# 19_PCIE.net
KiCad netlist of a schematic drawn in Altium Designer
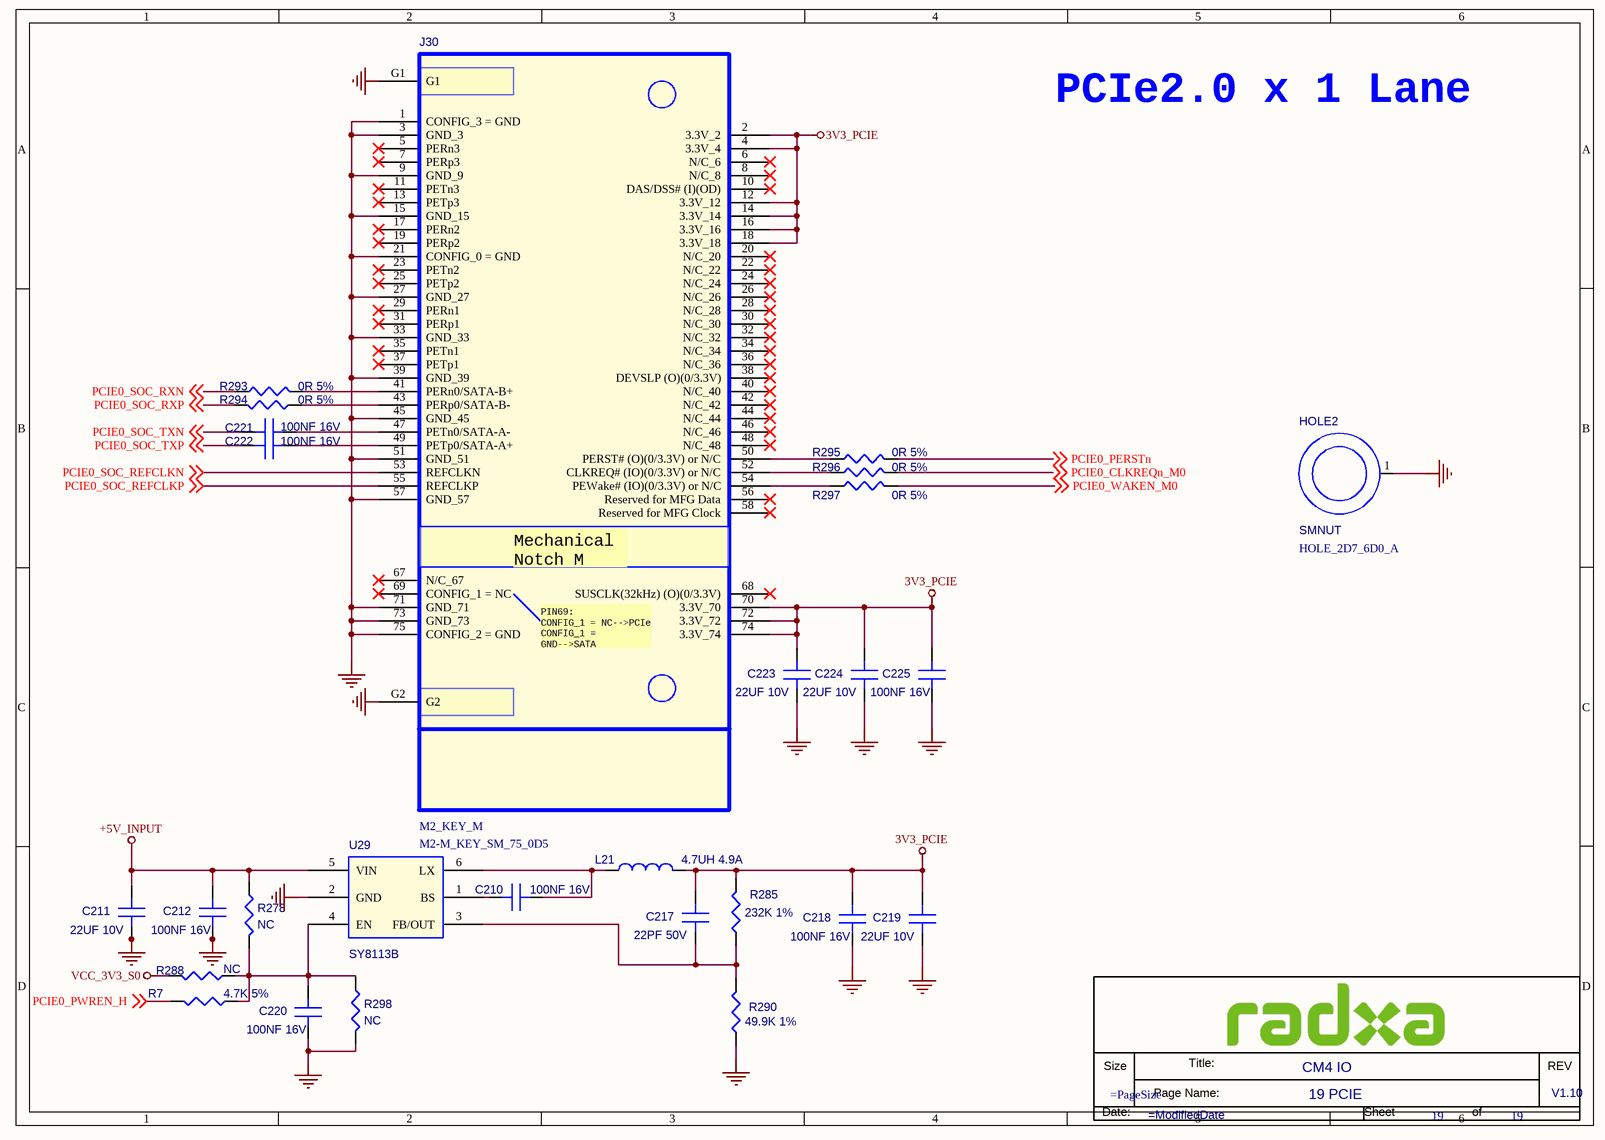
[diagram p0: 19 PCIE.SchDoc]

(export (version "E")
  (design (tool "Eeschema 10.0.6"))
  (components
    (comp (ref "C210")
      (value "100NF 16V")
      (footprint "C0201")
      (description "SMD  0201  100NF  16V  X5R  ±20%  ROHS")
      (fields (field (name "PART NUMBER") "A1C01.00099"))
      (libsource (lib "*") (part "C"))
    )
    (comp (ref "C211")
      (value "22UF 10V")
      (footprint "C0603")
      (description "SMD  0603  22UF  10V  X5R  ±10%  ROHS")
      (fields (field (name "PART NUMBER") "A1C01.00296"))
      (libsource (lib "*") (part "C"))
    )
    (comp (ref "C212")
      (value "100NF 16V")
      (footprint "C0201")
      (description "SMD  0201  100NF  16V  X5R  ±20%  ROHS")
      (fields (field (name "PART NUMBER") "A1C01.00099"))
      (libsource (lib "*") (part "C"))
    )
    (comp (ref "C217")
      (value "22PF 50V")
      (footprint "C0201")
      (description "SMD  0201  22PF  50V  NPO  ±5%  ROHS")
      (fields (field (name "PART NUMBER") "A1C01.00021"))
      (libsource (lib "*") (part "C"))
    )
    (comp (ref "C218")
      (value "100NF 16V")
      (footprint "C0201")
      (description "SMD  0201  100NF  16V  X5R  ±20%  ROHS")
      (fields (field (name "PART NUMBER") "A1C01.00099"))
      (libsource (lib "*") (part "C"))
    )
    (comp (ref "C219")
      (value "22UF 10V")
      (footprint "C0603")
      (description "SMD  0603  22UF  10V  X5R  ±10%  ROHS")
      (fields (field (name "PART NUMBER") "A1C01.00296"))
      (libsource (lib "*") (part "C"))
    )
    (comp (ref "C220")
      (value "100NF 16V")
      (footprint "C0201")
      (description "SMD  0201  100NF  16V  X5R  ±20%  ROHS")
      (fields (field (name "PART NUMBER") "A1C01.00099"))
      (libsource (lib "*") (part "C"))
    )
    (comp (ref "C221")
      (value "100NF 16V")
      (footprint "C0201")
      (description "SMD  0201  100NF  16V  X5R  ±20%  ROHS")
      (fields (field (name "PART NUMBER") "A1C01.00099"))
      (libsource (lib "*") (part "C"))
    )
    (comp (ref "C222")
      (value "100NF 16V")
      (footprint "C0201")
      (description "SMD  0201  100NF  16V  X5R  ±20%  ROHS")
      (fields (field (name "PART NUMBER") "A1C01.00099"))
      (libsource (lib "*") (part "C"))
    )
    (comp (ref "C223")
      (value "22UF 10V")
      (footprint "C0603")
      (description "SMD  0603  22UF  10V  X5R  ±10%  ROHS")
      (fields (field (name "PART NUMBER") "A1C01.00296"))
      (libsource (lib "*") (part "C"))
    )
    (comp (ref "C224")
      (value "22UF 10V")
      (footprint "C0603")
      (description "SMD  0603  22UF  10V  X5R  ±10%  ROHS")
      (fields (field (name "PART NUMBER") "A1C01.00296"))
      (libsource (lib "*") (part "C"))
    )
    (comp (ref "C225")
      (value "100NF 16V")
      (footprint "C0201")
      (description "SMD  0201  100NF  16V  X5R  ±20%  ROHS")
      (fields (field (name "PART NUMBER") "A1C01.00099"))
      (libsource (lib "*") (part "C"))
    )
    (comp (ref "HOLE2")
      (value "SMNUT")
      (footprint "HOLE_2D7_6D0_A")
      (fields (field (name "PART NUMBER") "A1S01.00008") (field (name "PCB FOOTPRINT") "HOLE_2D7_6D0_A"))
      (libsource (lib "*") (part "SMNUT"))
    )
    (comp (ref "J30")
      (value "M2_KEY_M")
      (footprint "M2-M_KEY_SM_75_0D5")
      (description "SMD  母座  75PIN  180度  0.5mm脚距  M.2  M KEY  H8.5  黑色  ROHS")
      (fields (field (name "PART NUMBER") "A1J01.00045") (field (name "PCB FOOTPRINT") "M2-M_KEY_SM_75_0D5"))
      (libsource (lib "*") (part "M2_KEY_M"))
    )
    (comp (ref "L21")
      (value "4.7UH 4.9A")
      (footprint "L_4020")
      (description "SMD  带屏蔽  4*4*2mm  4.7UH  4.9A  ±20%  RXWHJ4020-4R7MT  ROHS")
      (fields (field (name "PART NUMBER") "A1L01.00026"))
      (libsource (lib "*") (part "L"))
    )
    (comp (ref "R7")
      (value "4.7K 5%")
      (footprint "R0402")
      (description "SMD  0201  4.7K  1/20W  ±5%  ROHS")
      (fields (field (name "PART NUMBER") "A1R01.00014"))
      (libsource (lib "*") (part "R"))
    )
    (comp (ref "R278")
      (value "NC")
      (footprint "R0402")
      (description "SMD  0201  10K  1/20W  ±5%  ROHS")
      (fields (field (name "PART NUMBER") "A1R01.00012"))
      (libsource (lib "*") (part "R"))
    )
    (comp (ref "R285")
      (value "232K 1%")
      (footprint "R0402")
      (description "SMD  0201  232K  1/20W  ±1%  ROHS")
      (fields (field (name "PART NUMBER") "A1R01.00189"))
      (libsource (lib "*") (part "R"))
    )
    (comp (ref "R288")
      (value "NC")
      (footprint "R0402")
      (description "SMD  0201  10K  1/20W  ±5%  ROHS")
      (fields (field (name "PART NUMBER") "A1R01.00012"))
      (libsource (lib "*") (part "R"))
    )
    (comp (ref "R290")
      (value "49.9K 1%")
      (footprint "R0402")
      (description "SMD  0201  49.9K  1/20W  ±1%  ROHS")
      (fields (field (name "PART NUMBER") "A1R01.00207"))
      (libsource (lib "*") (part "R"))
    )
    (comp (ref "R293")
      (value "0R 5%")
      (footprint "R0402")
      (description "SMD  0201  0R  1/20W  ±5%  ROHS")
      (fields (field (name "PART NUMBER") "A1R01.00027"))
      (libsource (lib "*") (part "R"))
    )
    (comp (ref "R294")
      (value "0R 5%")
      (footprint "R0402")
      (description "SMD  0201  0R  1/20W  ±5%  ROHS")
      (fields (field (name "PART NUMBER") "A1R01.00027"))
      (libsource (lib "*") (part "R"))
    )
    (comp (ref "R295")
      (value "0R 5%")
      (footprint "R0402")
      (description "SMD  0201  0R  1/20W  ±5%  ROHS")
      (fields (field (name "PART NUMBER") "A1R01.00027"))
      (libsource (lib "*") (part "R"))
    )
    (comp (ref "R296")
      (value "0R 5%")
      (footprint "R0402")
      (description "SMD  0201  0R  1/20W  ±5%  ROHS")
      (fields (field (name "PART NUMBER") "A1R01.00027"))
      (libsource (lib "*") (part "R"))
    )
    (comp (ref "R297")
      (value "0R 5%")
      (footprint "R0402")
      (description "SMD  0201  0R  1/20W  ±5%  ROHS")
      (fields (field (name "PART NUMBER") "A1R01.00027"))
      (libsource (lib "*") (part "R"))
    )
    (comp (ref "R298")
      (value "NC")
      (footprint "R0402")
      (description "SMD  0201  10K  1/20W  ±5%  ROHS")
      (fields (field (name "PART NUMBER") "A1R01.00012"))
      (libsource (lib "*") (part "R"))
    )
    (comp (ref "U29")
      (value "SY8113B")
      (footprint "SOT23_6")
      (description "SMD  DCDC  SY8113BADC  SOT23-6  silergy(矽力杰)  ROHS")
      (fields (field (name "PART NUMBER") "A1I01.00093"))
      (libsource (lib "*") (part "SY8113B"))
    )
  )
  (nets
    (net (code "1") (name "+5V_INPUT") (class "Default")
      (node (ref "C211") (pin "1") (pinfunction "A_1") (pintype "passive"))
      (node (ref "C212") (pin "1") (pinfunction "A_1") (pintype "passive"))
      (node (ref "R278") (pin "2") (pinfunction "2_2") (pintype "passive"))
      (node (ref "U29") (pin "5") (pinfunction "VIN_5") (pintype "passive"))
    )
    (net (code "2") (name "3V3_PCIE") (class "Default")
      (node (ref "C217") (pin "1") (pinfunction "A_1") (pintype "passive"))
      (node (ref "C218") (pin "1") (pinfunction "A_1") (pintype "passive"))
      (node (ref "C219") (pin "1") (pinfunction "A_1") (pintype "passive"))
      (node (ref "C223") (pin "1") (pinfunction "A_1") (pintype "passive"))
      (node (ref "C224") (pin "1") (pinfunction "A_1") (pintype "passive"))
      (node (ref "C225") (pin "1") (pinfunction "A_1") (pintype "passive"))
      (node (ref "J30") (pin "12") (pinfunction "3.3V_12_12") (pintype "passive"))
      (node (ref "J30") (pin "14") (pinfunction "3.3V_14_14") (pintype "passive"))
      (node (ref "J30") (pin "16") (pinfunction "3.3V_16_16") (pintype "passive"))
      (node (ref "J30") (pin "18") (pinfunction "3.3V_18_18") (pintype "passive"))
      (node (ref "J30") (pin "2") (pinfunction "3.3V_2_2") (pintype "passive"))
      (node (ref "J30") (pin "4") (pinfunction "3.3V_4_4") (pintype "passive"))
      (node (ref "J30") (pin "70") (pinfunction "3.3V_70_70") (pintype "passive"))
      (node (ref "J30") (pin "72") (pinfunction "3.3V_72_72") (pintype "passive"))
      (node (ref "J30") (pin "74") (pinfunction "3.3V_74_74") (pintype "passive"))
      (node (ref "L21") (pin "2") (pinfunction "2_2") (pintype "passive"))
      (node (ref "R285") (pin "1") (pinfunction "1_1") (pintype "passive"))
    )
    (net (code "3") (name "GND") (class "Default")
      (node (ref "C211") (pin "2") (pinfunction "B_2") (pintype "passive"))
      (node (ref "C212") (pin "2") (pinfunction "B_2") (pintype "passive"))
      (node (ref "C218") (pin "2") (pinfunction "B_2") (pintype "passive"))
      (node (ref "C219") (pin "2") (pinfunction "B_2") (pintype "passive"))
      (node (ref "C220") (pin "2") (pinfunction "B_2") (pintype "passive"))
      (node (ref "C223") (pin "2") (pinfunction "B_2") (pintype "passive"))
      (node (ref "C224") (pin "2") (pinfunction "B_2") (pintype "passive"))
      (node (ref "C225") (pin "2") (pinfunction "B_2") (pintype "passive"))
      (node (ref "HOLE2") (pin "1") (pinfunction "1_1") (pintype "passive"))
      (node (ref "J30") (pin "1") (pinfunction "CONFIG_3_=_GND_1") (pintype "passive"))
      (node (ref "J30") (pin "15") (pinfunction "GND_15_15") (pintype "passive"))
      (node (ref "J30") (pin "21") (pinfunction "CONFIG_0_=_GND_21") (pintype "passive"))
      (node (ref "J30") (pin "27") (pinfunction "GND_27_27") (pintype "passive"))
      (node (ref "J30") (pin "3") (pinfunction "GND_3_3") (pintype "passive"))
      (node (ref "J30") (pin "33") (pinfunction "GND_33_33") (pintype "passive"))
      (node (ref "J30") (pin "39") (pinfunction "GND_39_39") (pintype "passive"))
      (node (ref "J30") (pin "45") (pinfunction "GND_45_45") (pintype "passive"))
      (node (ref "J30") (pin "51") (pinfunction "GND_51_51") (pintype "passive"))
      (node (ref "J30") (pin "57") (pinfunction "GND_57_57") (pintype "passive"))
      (node (ref "J30") (pin "71") (pinfunction "GND_71_71") (pintype "passive"))
      (node (ref "J30") (pin "73") (pinfunction "GND_73_73") (pintype "passive"))
      (node (ref "J30") (pin "75") (pinfunction "CONFIG_2_=_GND_75") (pintype "passive"))
      (node (ref "J30") (pin "9") (pinfunction "GND_9_9") (pintype "passive"))
      (node (ref "J30") (pin "G1") (pinfunction "G1_G1") (pintype "passive"))
      (node (ref "J30") (pin "G2") (pinfunction "G2_G2") (pintype "passive"))
      (node (ref "R290") (pin "2") (pinfunction "2_2") (pintype "passive"))
      (node (ref "R298") (pin "1") (pinfunction "1_1") (pintype "passive"))
      (node (ref "U29") (pin "2") (pinfunction "GND_2") (pintype "passive"))
    )
    (net (code "4") (name "Net-(C210-A)") (class "Default")
      (node (ref "C210") (pin "1") (pinfunction "A_1") (pintype "passive"))
      (node (ref "U29") (pin "1") (pinfunction "BS_1") (pintype "passive"))
    )
    (net (code "5") (name "Net-(C210-B)") (class "Default")
      (node (ref "C210") (pin "2") (pinfunction "B_2") (pintype "passive"))
      (node (ref "L21") (pin "1") (pinfunction "1_1") (pintype "passive"))
      (node (ref "U29") (pin "6") (pinfunction "LX_6") (pintype "passive"))
    )
    (net (code "6") (name "Net-(C217-B)") (class "Default")
      (node (ref "C217") (pin "2") (pinfunction "B_2") (pintype "passive"))
      (node (ref "R285") (pin "2") (pinfunction "2_2") (pintype "passive"))
      (node (ref "R290") (pin "1") (pinfunction "1_1") (pintype "passive"))
      (node (ref "U29") (pin "3") (pinfunction "FB/OUT_3") (pintype "passive"))
    )
    (net (code "7") (name "Net-(C220-A)") (class "Default")
      (node (ref "C220") (pin "1") (pinfunction "A_1") (pintype "passive"))
      (node (ref "R278") (pin "1") (pinfunction "1_1") (pintype "passive"))
      (node (ref "R288") (pin "2") (pinfunction "2_2") (pintype "passive"))
      (node (ref "R298") (pin "2") (pinfunction "2_2") (pintype "passive"))
      (node (ref "R7") (pin "2") (pinfunction "2_2") (pintype "passive"))
      (node (ref "U29") (pin "4") (pinfunction "EN_4") (pintype "passive"))
    )
    (net (code "8") (name "Net-(C221-B)") (class "Default")
      (node (ref "C221") (pin "2") (pinfunction "B_2") (pintype "passive"))
      (node (ref "J30") (pin "47") (pinfunction "PETn0/SATA-A-_47") (pintype "passive"))
    )
    (net (code "9") (name "Net-(C222-B)") (class "Default")
      (node (ref "C222") (pin "2") (pinfunction "B_2") (pintype "passive"))
      (node (ref "J30") (pin "49") (pinfunction "PETp0/SATA-A+_49") (pintype "passive"))
    )
    (net (code "10") (name "Net-(J30-CLKREQ#_(IO)(0{slash}3.3V)_or_N{slash}C)") (class "Default")
      (node (ref "J30") (pin "52") (pinfunction "CLKREQ#_(IO)(0/3.3V)_or_N/C_52") (pintype "passive"))
      (node (ref "R296") (pin "1") (pinfunction "1_1") (pintype "passive"))
    )
    (net (code "11") (name "Net-(J30-PERST#_(O)(0{slash}3.3V)_or_N{slash}C)") (class "Default")
      (node (ref "J30") (pin "50") (pinfunction "PERST#_(O)(0/3.3V)_or_N/C_50") (pintype "passive"))
      (node (ref "R295") (pin "1") (pinfunction "1_1") (pintype "passive"))
    )
    (net (code "12") (name "Net-(J30-PERn0{slash}SATA-B+)") (class "Default")
      (node (ref "J30") (pin "41") (pinfunction "PERn0/SATA-B+_41") (pintype "passive"))
      (node (ref "R293") (pin "2") (pinfunction "2_2") (pintype "passive"))
    )
    (net (code "13") (name "Net-(J30-PERp0{slash}SATA-B-)") (class "Default")
      (node (ref "J30") (pin "43") (pinfunction "PERp0/SATA-B-_43") (pintype "passive"))
      (node (ref "R294") (pin "2") (pinfunction "2_2") (pintype "passive"))
    )
    (net (code "14") (name "Net-(J30-PEWake#_(IO)(0{slash}3.3V)_or_N{slash}C)") (class "Default")
      (node (ref "J30") (pin "54") (pinfunction "PEWake#_(IO)(0/3.3V)_or_N/C_54") (pintype "passive"))
      (node (ref "R297") (pin "1") (pinfunction "1_1") (pintype "passive"))
    )
    (net (code "15") (name "PCIE0_CLKREQn_M0") (class "Default")
      (node (ref "R296") (pin "2") (pinfunction "2_2") (pintype "passive"))
    )
    (net (code "16") (name "PCIE0_PERSTn") (class "Default")
      (node (ref "R295") (pin "2") (pinfunction "2_2") (pintype "passive"))
    )
    (net (code "17") (name "PCIE0_PWREN_H") (class "Default")
      (node (ref "R7") (pin "1") (pinfunction "1_1") (pintype "passive"))
    )
    (net (code "18") (name "PCIE0_SOC_REFCLKN") (class "Default")
      (node (ref "J30") (pin "53") (pinfunction "REFCLKN_53") (pintype "passive"))
    )
    (net (code "19") (name "PCIE0_SOC_REFCLKP") (class "Default")
      (node (ref "J30") (pin "55") (pinfunction "REFCLKP_55") (pintype "passive"))
    )
    (net (code "20") (name "PCIE0_SOC_RXN") (class "Default")
      (node (ref "R293") (pin "1") (pinfunction "1_1") (pintype "passive"))
    )
    (net (code "21") (name "PCIE0_SOC_RXP") (class "Default")
      (node (ref "R294") (pin "1") (pinfunction "1_1") (pintype "passive"))
    )
    (net (code "22") (name "PCIE0_SOC_TXN") (class "Default")
      (node (ref "C221") (pin "1") (pinfunction "A_1") (pintype "passive"))
    )
    (net (code "23") (name "PCIE0_SOC_TXP") (class "Default")
      (node (ref "C222") (pin "1") (pinfunction "A_1") (pintype "passive"))
    )
    (net (code "24") (name "PCIE0_WAKEN_M0") (class "Default")
      (node (ref "R297") (pin "2") (pinfunction "2_2") (pintype "passive"))
    )
    (net (code "25") (name "VCC_3V3_S0") (class "Default")
      (node (ref "R288") (pin "1") (pinfunction "1_1") (pintype "passive"))
    )
    (net (code "26") (name "unconnected-(J30-CONFIG_1_=_NC-Pad69)") (class "Default")
      (node (ref "J30") (pin "69") (pinfunction "CONFIG_1_=_NC_69") (pintype "passive+no_connect"))
    )
    (net (code "27") (name "unconnected-(J30-DAS{slash}DSS#_(I)(OD)-Pad10)") (class "Default")
      (node (ref "J30") (pin "10") (pinfunction "DAS/DSS#_(I)(OD)_10") (pintype "passive+no_connect"))
    )
    (net (code "28") (name "unconnected-(J30-DEVSLP_(O)(0{slash}3.3V)-Pad38)") (class "Default")
      (node (ref "J30") (pin "38") (pinfunction "DEVSLP_(O)(0/3.3V)_38") (pintype "passive+no_connect"))
    )
    (net (code "29") (name "unconnected-(J30-N{slash}C_6-Pad6)") (class "Default")
      (node (ref "J30") (pin "6") (pinfunction "N/C_6_6") (pintype "passive+no_connect"))
    )
    (net (code "30") (name "unconnected-(J30-N{slash}C_8-Pad8)") (class "Default")
      (node (ref "J30") (pin "8") (pinfunction "N/C_8_8") (pintype "passive+no_connect"))
    )
    (net (code "31") (name "unconnected-(J30-N{slash}C_20-Pad20)") (class "Default")
      (node (ref "J30") (pin "20") (pinfunction "N/C_20_20") (pintype "passive+no_connect"))
    )
    (net (code "32") (name "unconnected-(J30-N{slash}C_22-Pad22)") (class "Default")
      (node (ref "J30") (pin "22") (pinfunction "N/C_22_22") (pintype "passive+no_connect"))
    )
    (net (code "33") (name "unconnected-(J30-N{slash}C_24-Pad24)") (class "Default")
      (node (ref "J30") (pin "24") (pinfunction "N/C_24_24") (pintype "passive+no_connect"))
    )
    (net (code "34") (name "unconnected-(J30-N{slash}C_26-Pad26)") (class "Default")
      (node (ref "J30") (pin "26") (pinfunction "N/C_26_26") (pintype "passive+no_connect"))
    )
    (net (code "35") (name "unconnected-(J30-N{slash}C_28-Pad28)") (class "Default")
      (node (ref "J30") (pin "28") (pinfunction "N/C_28_28") (pintype "passive+no_connect"))
    )
    (net (code "36") (name "unconnected-(J30-N{slash}C_30-Pad30)") (class "Default")
      (node (ref "J30") (pin "30") (pinfunction "N/C_30_30") (pintype "passive+no_connect"))
    )
    (net (code "37") (name "unconnected-(J30-N{slash}C_32-Pad32)") (class "Default")
      (node (ref "J30") (pin "32") (pinfunction "N/C_32_32") (pintype "passive+no_connect"))
    )
    (net (code "38") (name "unconnected-(J30-N{slash}C_34-Pad34)") (class "Default")
      (node (ref "J30") (pin "34") (pinfunction "N/C_34_34") (pintype "passive+no_connect"))
    )
    (net (code "39") (name "unconnected-(J30-N{slash}C_36-Pad36)") (class "Default")
      (node (ref "J30") (pin "36") (pinfunction "N/C_36_36") (pintype "passive+no_connect"))
    )
    (net (code "40") (name "unconnected-(J30-N{slash}C_40-Pad40)") (class "Default")
      (node (ref "J30") (pin "40") (pinfunction "N/C_40_40") (pintype "passive+no_connect"))
    )
    (net (code "41") (name "unconnected-(J30-N{slash}C_42-Pad42)") (class "Default")
      (node (ref "J30") (pin "42") (pinfunction "N/C_42_42") (pintype "passive+no_connect"))
    )
    (net (code "42") (name "unconnected-(J30-N{slash}C_44-Pad44)") (class "Default")
      (node (ref "J30") (pin "44") (pinfunction "N/C_44_44") (pintype "passive+no_connect"))
    )
    (net (code "43") (name "unconnected-(J30-N{slash}C_46-Pad46)") (class "Default")
      (node (ref "J30") (pin "46") (pinfunction "N/C_46_46") (pintype "passive+no_connect"))
    )
    (net (code "44") (name "unconnected-(J30-N{slash}C_48-Pad48)") (class "Default")
      (node (ref "J30") (pin "48") (pinfunction "N/C_48_48") (pintype "passive+no_connect"))
    )
    (net (code "45") (name "unconnected-(J30-N{slash}C_67-Pad67)") (class "Default")
      (node (ref "J30") (pin "67") (pinfunction "N/C_67_67") (pintype "passive+no_connect"))
    )
    (net (code "46") (name "unconnected-(J30-PERn1-Pad29)") (class "Default")
      (node (ref "J30") (pin "29") (pinfunction "PERn1_29") (pintype "passive+no_connect"))
    )
    (net (code "47") (name "unconnected-(J30-PERn2-Pad17)") (class "Default")
      (node (ref "J30") (pin "17") (pinfunction "PERn2_17") (pintype "passive+no_connect"))
    )
    (net (code "48") (name "unconnected-(J30-PERn3-Pad5)") (class "Default")
      (node (ref "J30") (pin "5") (pinfunction "PERn3_5") (pintype "passive+no_connect"))
    )
    (net (code "49") (name "unconnected-(J30-PERp1-Pad31)") (class "Default")
      (node (ref "J30") (pin "31") (pinfunction "PERp1_31") (pintype "passive+no_connect"))
    )
    (net (code "50") (name "unconnected-(J30-PERp2-Pad19)") (class "Default")
      (node (ref "J30") (pin "19") (pinfunction "PERp2_19") (pintype "passive+no_connect"))
    )
    (net (code "51") (name "unconnected-(J30-PERp3-Pad7)") (class "Default")
      (node (ref "J30") (pin "7") (pinfunction "PERp3_7") (pintype "passive+no_connect"))
    )
    (net (code "52") (name "unconnected-(J30-PETn1-Pad35)") (class "Default")
      (node (ref "J30") (pin "35") (pinfunction "PETn1_35") (pintype "passive+no_connect"))
    )
    (net (code "53") (name "unconnected-(J30-PETn2-Pad23)") (class "Default")
      (node (ref "J30") (pin "23") (pinfunction "PETn2_23") (pintype "passive+no_connect"))
    )
    (net (code "54") (name "unconnected-(J30-PETn3-Pad11)") (class "Default")
      (node (ref "J30") (pin "11") (pinfunction "PETn3_11") (pintype "passive+no_connect"))
    )
    (net (code "55") (name "unconnected-(J30-PETp1-Pad37)") (class "Default")
      (node (ref "J30") (pin "37") (pinfunction "PETp1_37") (pintype "passive+no_connect"))
    )
    (net (code "56") (name "unconnected-(J30-PETp2-Pad25)") (class "Default")
      (node (ref "J30") (pin "25") (pinfunction "PETp2_25") (pintype "passive+no_connect"))
    )
    (net (code "57") (name "unconnected-(J30-PETp3-Pad13)") (class "Default")
      (node (ref "J30") (pin "13") (pinfunction "PETp3_13") (pintype "passive+no_connect"))
    )
    (net (code "58") (name "unconnected-(J30-Reserved_for_MFG_Clock-Pad58)") (class "Default")
      (node (ref "J30") (pin "58") (pinfunction "Reserved_for_MFG_Clock_58") (pintype "passive+no_connect"))
    )
    (net (code "59") (name "unconnected-(J30-Reserved_for_MFG_Data-Pad56)") (class "Default")
      (node (ref "J30") (pin "56") (pinfunction "Reserved_for_MFG_Data_56") (pintype "passive+no_connect"))
    )
    (net (code "60") (name "unconnected-(J30-SUSCLK(32kHz)_(O)(0{slash}3.3V)-Pad68)") (class "Default")
      (node (ref "J30") (pin "68") (pinfunction "SUSCLK(32kHz)_(O)(0/3.3V)_68") (pintype "passive+no_connect"))
    )
  )
)
